# LEDArray.net
KiCad netlist of a schematic drawn in Altium Designer
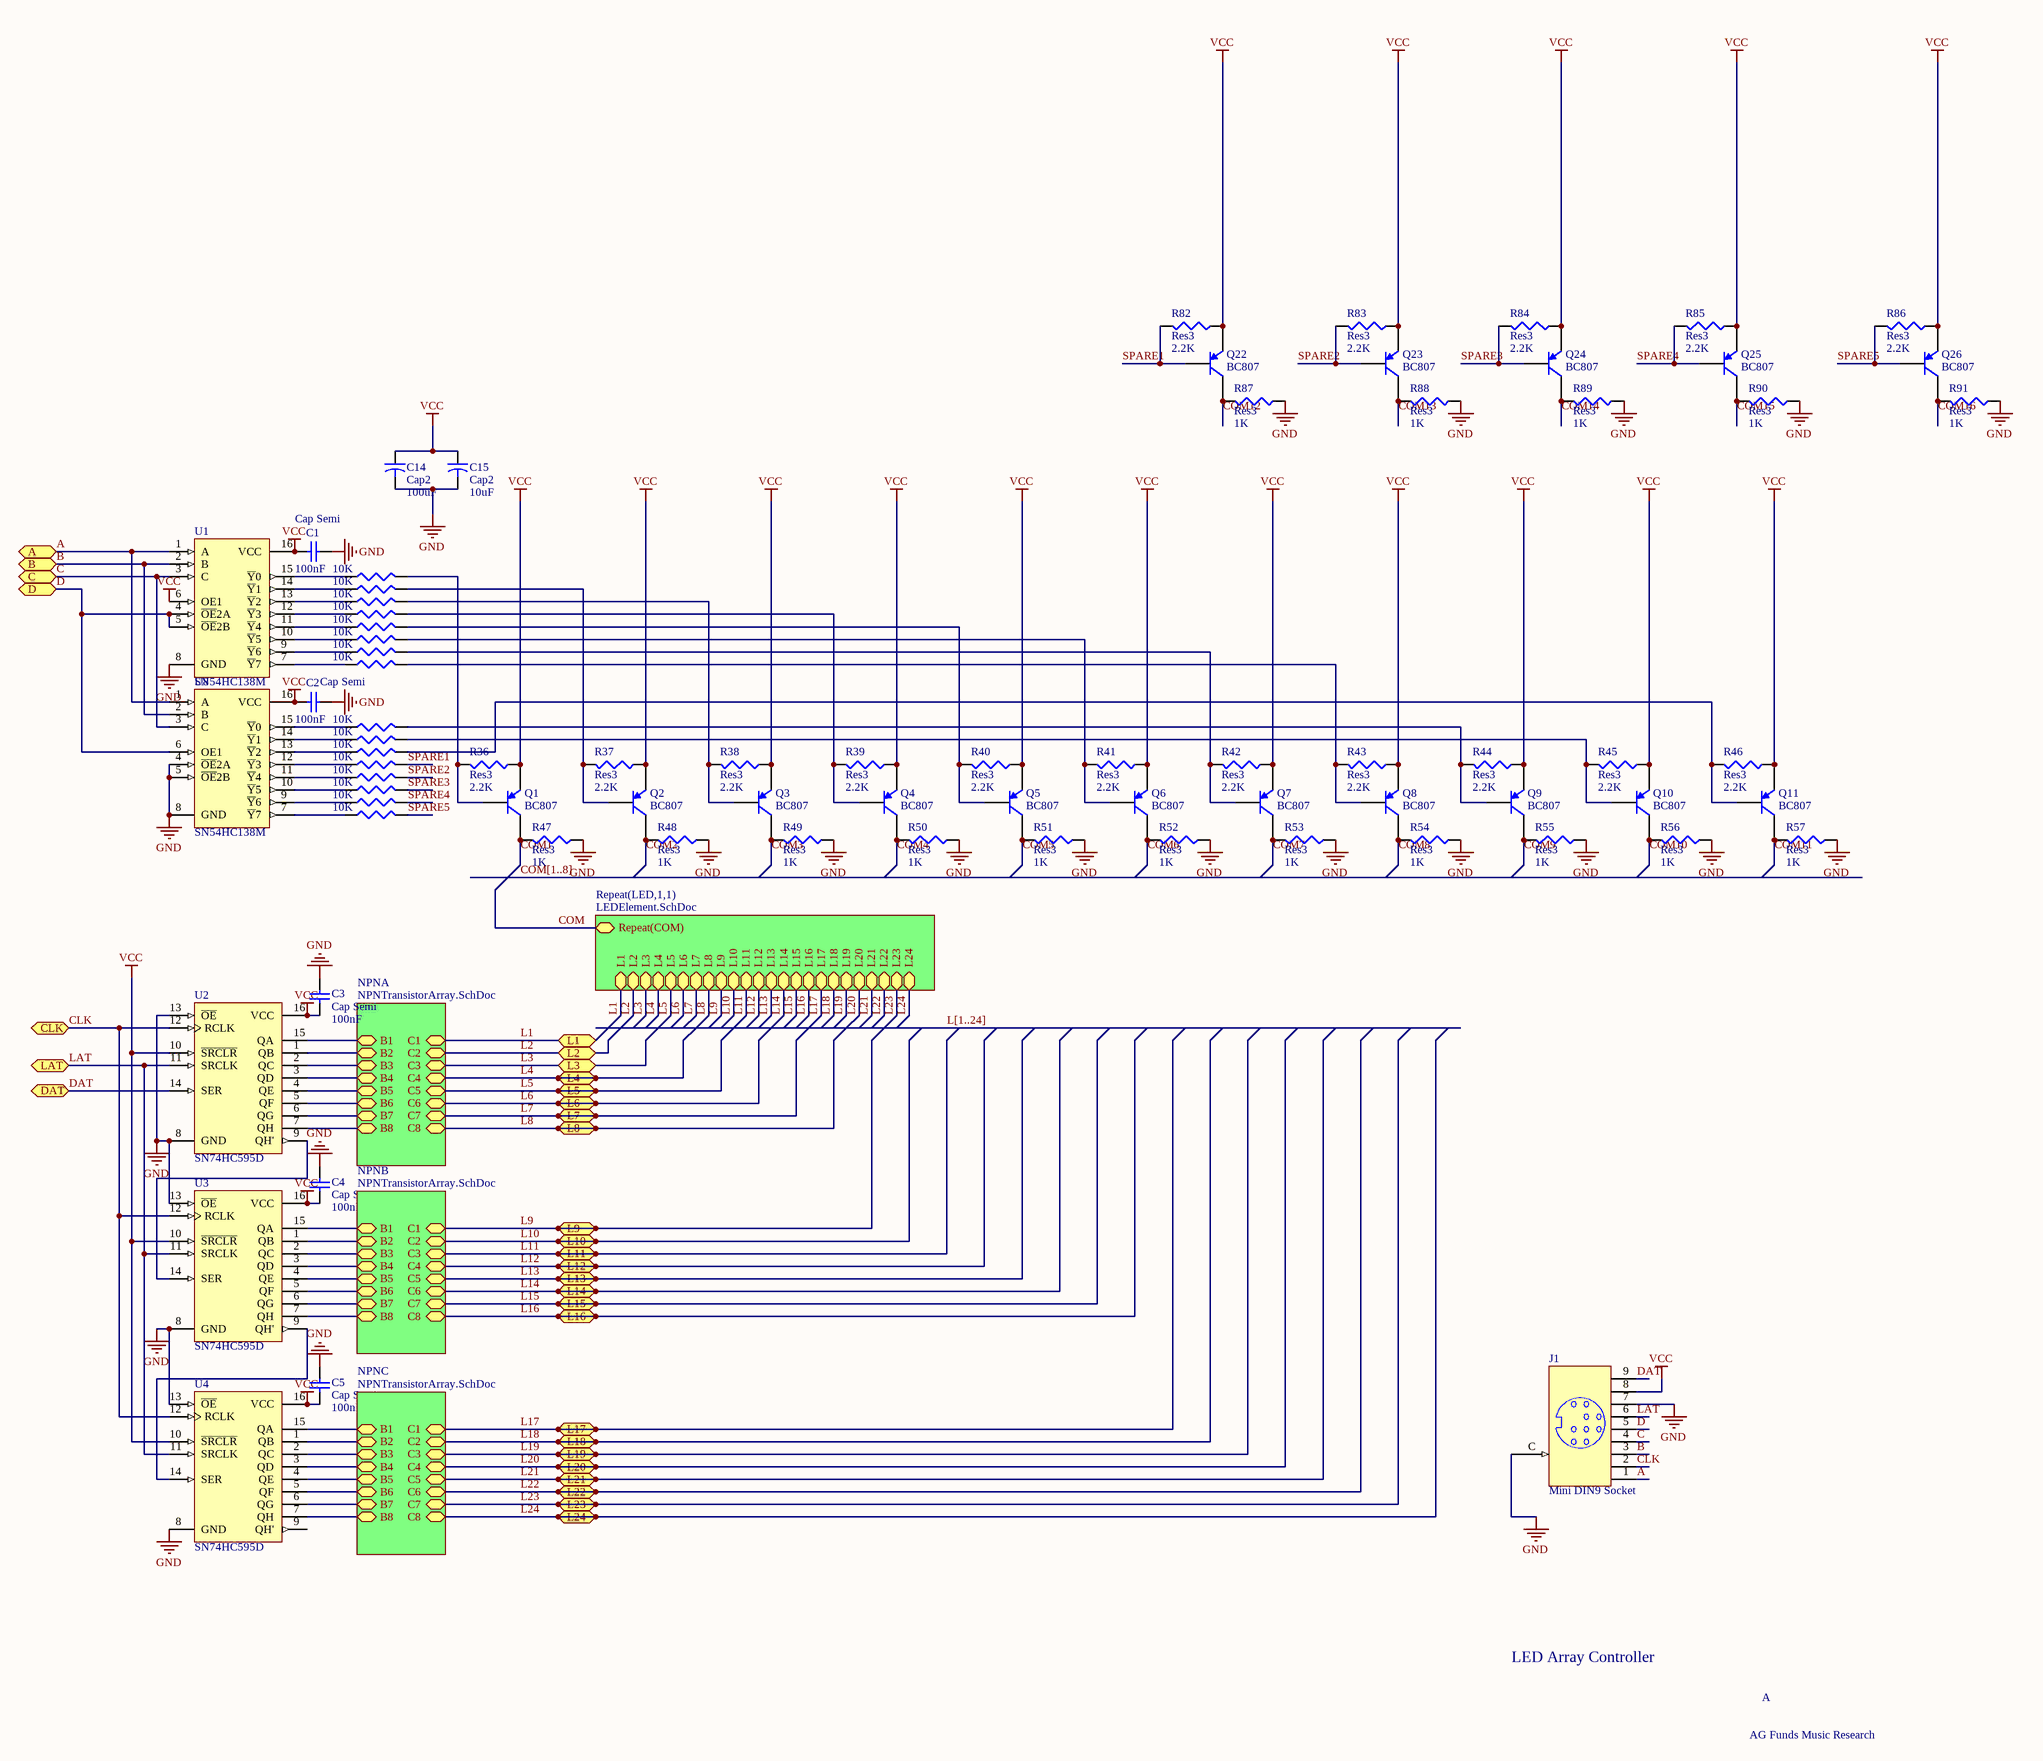
[diagram p0: LEDArray.SchDoc]

(export (version "E")
  (design (tool "Eeschema 10.0.6"))
  (components
    (comp (ref "C1")
      (value "Cap Semi")
      (footprint "1608[0603]")
      (description "Capacitor (Semiconductor SIM Model)")
      (fields (field (name "ALTIUM_VALUE") "100nF") (field (name "PUBLISHER") "Altium Limited"))
      (libsource (lib "Miscellaneous Devices") (part "Cap Semi"))
    )
    (comp (ref "C2")
      (value "Cap Semi")
      (footprint "1608[0603]")
      (description "Capacitor (Semiconductor SIM Model)")
      (fields (field (name "ALTIUM_VALUE") "100nF") (field (name "PUBLISHER") "Altium Limited"))
      (libsource (lib "Miscellaneous Devices") (part "Cap Semi"))
    )
    (comp (ref "C3")
      (value "Cap Semi")
      (footprint "1608[0603]")
      (description "Capacitor (Semiconductor SIM Model)")
      (fields (field (name "ALTIUM_VALUE") "100nF") (field (name "PUBLISHER") "Altium Limited"))
      (libsource (lib "Miscellaneous Devices") (part "Cap Semi"))
    )
    (comp (ref "C4")
      (value "Cap Semi")
      (footprint "1608[0603]")
      (description "Capacitor (Semiconductor SIM Model)")
      (fields (field (name "ALTIUM_VALUE") "100nF") (field (name "PUBLISHER") "Altium Limited"))
      (libsource (lib "Miscellaneous Devices") (part "Cap Semi"))
    )
    (comp (ref "C5")
      (value "Cap Semi")
      (footprint "1608[0603]")
      (description "Capacitor (Semiconductor SIM Model)")
      (fields (field (name "ALTIUM_VALUE") "100nF") (field (name "PUBLISHER") "Altium Limited"))
      (libsource (lib "Miscellaneous Devices") (part "Cap Semi"))
    )
    (comp (ref "C14")
      (value "Cap2")
      (footprint "CAPR5-4X5")
      (description "Capacitor")
      (fields (field (name "ALTIUM_VALUE") "100uF") (field (name "PUBLISHER") "Altium Limited"))
      (libsource (lib "Miscellaneous Devices") (part "Cap2"))
    )
    (comp (ref "C15")
      (value "Cap2")
      (footprint "CAPR5-4X5")
      (description "Capacitor")
      (fields (field (name "ALTIUM_VALUE") "10uF") (field (name "PUBLISHER") "Altium Limited"))
      (libsource (lib "Miscellaneous Devices") (part "Cap2"))
    )
    (comp (ref "J1")
      (value "Mini DIN9 Socket")
      (footprint "RGBLED:9miniDIN")
      (description "CUI Inc. MD-90S MINIDIN9 PCB Mount Socket")
      (fields (field (name "PUBLISHER") "Altium Limited"))
      (libsource (lib "MIDIPiano_7") (part "mDIN9"))
    )
    (comp (ref "Q1")
      (value "BC807")
      (footprint "SOT23-3M")
      (description "BC807 PNP General Purpose Amplifier")
      (libsource (lib "MIDIPiano_7") (part "BC807"))
    )
    (comp (ref "Q2")
      (value "BC807")
      (footprint "SOT23-3M")
      (description "BC807 PNP General Purpose Amplifier")
      (libsource (lib "MIDIPiano_7") (part "BC807"))
    )
    (comp (ref "Q3")
      (value "BC807")
      (footprint "SOT23-3M")
      (description "BC807 PNP General Purpose Amplifier")
      (libsource (lib "MIDIPiano_7") (part "BC807"))
    )
    (comp (ref "Q4")
      (value "BC807")
      (footprint "SOT23-3M")
      (description "BC807 PNP General Purpose Amplifier")
      (libsource (lib "MIDIPiano_7") (part "BC807"))
    )
    (comp (ref "Q5")
      (value "BC807")
      (footprint "SOT23-3M")
      (description "BC807 PNP General Purpose Amplifier")
      (libsource (lib "MIDIPiano_7") (part "BC807"))
    )
    (comp (ref "Q6")
      (value "BC807")
      (footprint "SOT23-3M")
      (description "BC807 PNP General Purpose Amplifier")
      (libsource (lib "MIDIPiano_7") (part "BC807"))
    )
    (comp (ref "Q7")
      (value "BC807")
      (footprint "SOT23-3M")
      (description "BC807 PNP General Purpose Amplifier")
      (libsource (lib "MIDIPiano_7") (part "BC807"))
    )
    (comp (ref "Q8")
      (value "BC807")
      (footprint "SOT23-3M")
      (description "BC807 PNP General Purpose Amplifier")
      (libsource (lib "MIDIPiano_7") (part "BC807"))
    )
    (comp (ref "Q9")
      (value "BC807")
      (footprint "SOT23-3M")
      (description "BC807 PNP General Purpose Amplifier")
      (libsource (lib "MIDIPiano_7") (part "BC807"))
    )
    (comp (ref "Q10")
      (value "BC807")
      (footprint "SOT23-3M")
      (description "BC807 PNP General Purpose Amplifier")
      (libsource (lib "MIDIPiano_7") (part "BC807"))
    )
    (comp (ref "Q11")
      (value "BC807")
      (footprint "SOT23-3M")
      (description "BC807 PNP General Purpose Amplifier")
      (libsource (lib "MIDIPiano_7") (part "BC807"))
    )
    (comp (ref "Q22")
      (value "BC807")
      (footprint "SOT23-3M")
      (description "BC807 PNP General Purpose Amplifier")
      (libsource (lib "MIDIPiano_7") (part "BC807"))
    )
    (comp (ref "Q23")
      (value "BC807")
      (footprint "SOT23-3M")
      (description "BC807 PNP General Purpose Amplifier")
      (libsource (lib "MIDIPiano_7") (part "BC807"))
    )
    (comp (ref "Q24")
      (value "BC807")
      (footprint "SOT23-3M")
      (description "BC807 PNP General Purpose Amplifier")
      (libsource (lib "MIDIPiano_7") (part "BC807"))
    )
    (comp (ref "Q25")
      (value "BC807")
      (footprint "SOT23-3M")
      (description "BC807 PNP General Purpose Amplifier")
      (libsource (lib "MIDIPiano_7") (part "BC807"))
    )
    (comp (ref "Q26")
      (value "BC807")
      (footprint "SOT23-3M")
      (description "BC807 PNP General Purpose Amplifier")
      (libsource (lib "MIDIPiano_7") (part "BC807"))
    )
    (comp (ref "R25")
      (value "10K")
      (footprint "J1-0603")
      (description "Resistor")
      (fields (field (name "Comment") "Res3") (field (name "PUBLISHER") "Altium Limited"))
      (libsource (lib "Miscellaneous Devices") (part "Res3"))
    )
    (comp (ref "R26")
      (value "10K")
      (footprint "J1-0603")
      (description "Resistor")
      (fields (field (name "Comment") "Res3") (field (name "PUBLISHER") "Altium Limited"))
      (libsource (lib "Miscellaneous Devices") (part "Res3"))
    )
    (comp (ref "R27")
      (value "10K")
      (footprint "J1-0603")
      (description "Resistor")
      (fields (field (name "Comment") "Res3") (field (name "PUBLISHER") "Altium Limited"))
      (libsource (lib "Miscellaneous Devices") (part "Res3"))
    )
    (comp (ref "R28")
      (value "10K")
      (footprint "J1-0603")
      (description "Resistor")
      (fields (field (name "Comment") "Res3") (field (name "PUBLISHER") "Altium Limited"))
      (libsource (lib "Miscellaneous Devices") (part "Res3"))
    )
    (comp (ref "R29")
      (value "10K")
      (footprint "J1-0603")
      (description "Resistor")
      (fields (field (name "Comment") "Res3") (field (name "PUBLISHER") "Altium Limited"))
      (libsource (lib "Miscellaneous Devices") (part "Res3"))
    )
    (comp (ref "R30")
      (value "10K")
      (footprint "J1-0603")
      (description "Resistor")
      (fields (field (name "Comment") "Res3") (field (name "PUBLISHER") "Altium Limited"))
      (libsource (lib "Miscellaneous Devices") (part "Res3"))
    )
    (comp (ref "R31")
      (value "10K")
      (footprint "J1-0603")
      (description "Resistor")
      (fields (field (name "Comment") "Res3") (field (name "PUBLISHER") "Altium Limited"))
      (libsource (lib "Miscellaneous Devices") (part "Res3"))
    )
    (comp (ref "R32")
      (value "10K")
      (footprint "J1-0603")
      (description "Resistor")
      (fields (field (name "Comment") "Res3") (field (name "PUBLISHER") "Altium Limited"))
      (libsource (lib "Miscellaneous Devices") (part "Res3"))
    )
    (comp (ref "R33")
      (value "10K")
      (footprint "J1-0603")
      (description "Resistor")
      (fields (field (name "Comment") "Res3") (field (name "PUBLISHER") "Altium Limited"))
      (libsource (lib "Miscellaneous Devices") (part "Res3"))
    )
    (comp (ref "R34")
      (value "10K")
      (footprint "J1-0603")
      (description "Resistor")
      (fields (field (name "Comment") "Res3") (field (name "PUBLISHER") "Altium Limited"))
      (libsource (lib "Miscellaneous Devices") (part "Res3"))
    )
    (comp (ref "R35")
      (value "10K")
      (footprint "J1-0603")
      (description "Resistor")
      (fields (field (name "Comment") "Res3") (field (name "PUBLISHER") "Altium Limited"))
      (libsource (lib "Miscellaneous Devices") (part "Res3"))
    )
    (comp (ref "R36")
      (value "Res3")
      (footprint "J1-0603")
      (description "Resistor")
      (fields (field (name "ALTIUM_VALUE") "2.2K") (field (name "PUBLISHER") "Altium Limited"))
      (libsource (lib "Miscellaneous Devices") (part "Res3"))
    )
    (comp (ref "R37")
      (value "Res3")
      (footprint "J1-0603")
      (description "Resistor")
      (fields (field (name "ALTIUM_VALUE") "2.2K") (field (name "PUBLISHER") "Altium Limited"))
      (libsource (lib "Miscellaneous Devices") (part "Res3"))
    )
    (comp (ref "R38")
      (value "Res3")
      (footprint "J1-0603")
      (description "Resistor")
      (fields (field (name "ALTIUM_VALUE") "2.2K") (field (name "PUBLISHER") "Altium Limited"))
      (libsource (lib "Miscellaneous Devices") (part "Res3"))
    )
    (comp (ref "R39")
      (value "Res3")
      (footprint "J1-0603")
      (description "Resistor")
      (fields (field (name "ALTIUM_VALUE") "2.2K") (field (name "PUBLISHER") "Altium Limited"))
      (libsource (lib "Miscellaneous Devices") (part "Res3"))
    )
    (comp (ref "R40")
      (value "Res3")
      (footprint "J1-0603")
      (description "Resistor")
      (fields (field (name "ALTIUM_VALUE") "2.2K") (field (name "PUBLISHER") "Altium Limited"))
      (libsource (lib "Miscellaneous Devices") (part "Res3"))
    )
    (comp (ref "R41")
      (value "Res3")
      (footprint "J1-0603")
      (description "Resistor")
      (fields (field (name "ALTIUM_VALUE") "2.2K") (field (name "PUBLISHER") "Altium Limited"))
      (libsource (lib "Miscellaneous Devices") (part "Res3"))
    )
    (comp (ref "R42")
      (value "Res3")
      (footprint "J1-0603")
      (description "Resistor")
      (fields (field (name "ALTIUM_VALUE") "2.2K") (field (name "PUBLISHER") "Altium Limited"))
      (libsource (lib "Miscellaneous Devices") (part "Res3"))
    )
    (comp (ref "R43")
      (value "Res3")
      (footprint "J1-0603")
      (description "Resistor")
      (fields (field (name "ALTIUM_VALUE") "2.2K") (field (name "PUBLISHER") "Altium Limited"))
      (libsource (lib "Miscellaneous Devices") (part "Res3"))
    )
    (comp (ref "R44")
      (value "Res3")
      (footprint "J1-0603")
      (description "Resistor")
      (fields (field (name "ALTIUM_VALUE") "2.2K") (field (name "PUBLISHER") "Altium Limited"))
      (libsource (lib "Miscellaneous Devices") (part "Res3"))
    )
    (comp (ref "R45")
      (value "Res3")
      (footprint "J1-0603")
      (description "Resistor")
      (fields (field (name "ALTIUM_VALUE") "2.2K") (field (name "PUBLISHER") "Altium Limited"))
      (libsource (lib "Miscellaneous Devices") (part "Res3"))
    )
    (comp (ref "R46")
      (value "Res3")
      (footprint "J1-0603")
      (description "Resistor")
      (fields (field (name "ALTIUM_VALUE") "2.2K") (field (name "PUBLISHER") "Altium Limited"))
      (libsource (lib "Miscellaneous Devices") (part "Res3"))
    )
    (comp (ref "R47")
      (value "Res3")
      (footprint "J1-0603")
      (description "Resistor")
      (fields (field (name "ALTIUM_VALUE") "1K") (field (name "PUBLISHER") "Altium Limited"))
      (libsource (lib "Miscellaneous Devices") (part "Res3"))
    )
    (comp (ref "R48")
      (value "Res3")
      (footprint "J1-0603")
      (description "Resistor")
      (fields (field (name "ALTIUM_VALUE") "1K") (field (name "PUBLISHER") "Altium Limited"))
      (libsource (lib "Miscellaneous Devices") (part "Res3"))
    )
    (comp (ref "R49")
      (value "Res3")
      (footprint "J1-0603")
      (description "Resistor")
      (fields (field (name "ALTIUM_VALUE") "1K") (field (name "PUBLISHER") "Altium Limited"))
      (libsource (lib "Miscellaneous Devices") (part "Res3"))
    )
    (comp (ref "R50")
      (value "Res3")
      (footprint "J1-0603")
      (description "Resistor")
      (fields (field (name "ALTIUM_VALUE") "1K") (field (name "PUBLISHER") "Altium Limited"))
      (libsource (lib "Miscellaneous Devices") (part "Res3"))
    )
    (comp (ref "R51")
      (value "Res3")
      (footprint "J1-0603")
      (description "Resistor")
      (fields (field (name "ALTIUM_VALUE") "1K") (field (name "PUBLISHER") "Altium Limited"))
      (libsource (lib "Miscellaneous Devices") (part "Res3"))
    )
    (comp (ref "R52")
      (value "Res3")
      (footprint "J1-0603")
      (description "Resistor")
      (fields (field (name "ALTIUM_VALUE") "1K") (field (name "PUBLISHER") "Altium Limited"))
      (libsource (lib "Miscellaneous Devices") (part "Res3"))
    )
    (comp (ref "R53")
      (value "Res3")
      (footprint "J1-0603")
      (description "Resistor")
      (fields (field (name "ALTIUM_VALUE") "1K") (field (name "PUBLISHER") "Altium Limited"))
      (libsource (lib "Miscellaneous Devices") (part "Res3"))
    )
    (comp (ref "R54")
      (value "Res3")
      (footprint "J1-0603")
      (description "Resistor")
      (fields (field (name "ALTIUM_VALUE") "1K") (field (name "PUBLISHER") "Altium Limited"))
      (libsource (lib "Miscellaneous Devices") (part "Res3"))
    )
    (comp (ref "R55")
      (value "Res3")
      (footprint "J1-0603")
      (description "Resistor")
      (fields (field (name "ALTIUM_VALUE") "1K") (field (name "PUBLISHER") "Altium Limited"))
      (libsource (lib "Miscellaneous Devices") (part "Res3"))
    )
    (comp (ref "R56")
      (value "Res3")
      (footprint "J1-0603")
      (description "Resistor")
      (fields (field (name "ALTIUM_VALUE") "1K") (field (name "PUBLISHER") "Altium Limited"))
      (libsource (lib "Miscellaneous Devices") (part "Res3"))
    )
    (comp (ref "R57")
      (value "Res3")
      (footprint "J1-0603")
      (description "Resistor")
      (fields (field (name "ALTIUM_VALUE") "1K") (field (name "PUBLISHER") "Altium Limited"))
      (libsource (lib "Miscellaneous Devices") (part "Res3"))
    )
    (comp (ref "R82")
      (value "Res3")
      (footprint "J1-0603")
      (description "Resistor")
      (fields (field (name "ALTIUM_VALUE") "2.2K") (field (name "PUBLISHER") "Altium Limited"))
      (libsource (lib "Miscellaneous Devices") (part "Res3"))
    )
    (comp (ref "R83")
      (value "Res3")
      (footprint "J1-0603")
      (description "Resistor")
      (fields (field (name "ALTIUM_VALUE") "2.2K") (field (name "PUBLISHER") "Altium Limited"))
      (libsource (lib "Miscellaneous Devices") (part "Res3"))
    )
    (comp (ref "R84")
      (value "Res3")
      (footprint "J1-0603")
      (description "Resistor")
      (fields (field (name "ALTIUM_VALUE") "2.2K") (field (name "PUBLISHER") "Altium Limited"))
      (libsource (lib "Miscellaneous Devices") (part "Res3"))
    )
    (comp (ref "R85")
      (value "Res3")
      (footprint "J1-0603")
      (description "Resistor")
      (fields (field (name "ALTIUM_VALUE") "2.2K") (field (name "PUBLISHER") "Altium Limited"))
      (libsource (lib "Miscellaneous Devices") (part "Res3"))
    )
    (comp (ref "R86")
      (value "Res3")
      (footprint "J1-0603")
      (description "Resistor")
      (fields (field (name "ALTIUM_VALUE") "2.2K") (field (name "PUBLISHER") "Altium Limited"))
      (libsource (lib "Miscellaneous Devices") (part "Res3"))
    )
    (comp (ref "R87")
      (value "Res3")
      (footprint "J1-0603")
      (description "Resistor")
      (fields (field (name "ALTIUM_VALUE") "1K") (field (name "PUBLISHER") "Altium Limited"))
      (libsource (lib "Miscellaneous Devices") (part "Res3"))
    )
    (comp (ref "R88")
      (value "Res3")
      (footprint "J1-0603")
      (description "Resistor")
      (fields (field (name "ALTIUM_VALUE") "1K") (field (name "PUBLISHER") "Altium Limited"))
      (libsource (lib "Miscellaneous Devices") (part "Res3"))
    )
    (comp (ref "R89")
      (value "Res3")
      (footprint "J1-0603")
      (description "Resistor")
      (fields (field (name "ALTIUM_VALUE") "1K") (field (name "PUBLISHER") "Altium Limited"))
      (libsource (lib "Miscellaneous Devices") (part "Res3"))
    )
    (comp (ref "R90")
      (value "Res3")
      (footprint "J1-0603")
      (description "Resistor")
      (fields (field (name "ALTIUM_VALUE") "1K") (field (name "PUBLISHER") "Altium Limited"))
      (libsource (lib "Miscellaneous Devices") (part "Res3"))
    )
    (comp (ref "R91")
      (value "Res3")
      (footprint "J1-0603")
      (description "Resistor")
      (fields (field (name "ALTIUM_VALUE") "1K") (field (name "PUBLISHER") "Altium Limited"))
      (libsource (lib "Miscellaneous Devices") (part "Res3"))
    )
    (comp (ref "R92")
      (value "10K")
      (footprint "J1-0603")
      (description "Resistor")
      (fields (field (name "Comment") "Res3") (field (name "PUBLISHER") "Altium Limited"))
      (libsource (lib "Miscellaneous Devices") (part "Res3"))
    )
    (comp (ref "R93")
      (value "10K")
      (footprint "J1-0603")
      (description "Resistor")
      (fields (field (name "Comment") "Res3") (field (name "PUBLISHER") "Altium Limited"))
      (libsource (lib "Miscellaneous Devices") (part "Res3"))
    )
    (comp (ref "R94")
      (value "10K")
      (footprint "J1-0603")
      (description "Resistor")
      (fields (field (name "Comment") "Res3") (field (name "PUBLISHER") "Altium Limited"))
      (libsource (lib "Miscellaneous Devices") (part "Res3"))
    )
    (comp (ref "R95")
      (value "10K")
      (footprint "J1-0603")
      (description "Resistor")
      (fields (field (name "Comment") "Res3") (field (name "PUBLISHER") "Altium Limited"))
      (libsource (lib "Miscellaneous Devices") (part "Res3"))
    )
    (comp (ref "R96")
      (value "10K")
      (footprint "J1-0603")
      (description "Resistor")
      (fields (field (name "Comment") "Res3") (field (name "PUBLISHER") "Altium Limited"))
      (libsource (lib "Miscellaneous Devices") (part "Res3"))
    )
    (comp (ref "U1")
      (value "SN54HC138M")
      (footprint "SOIC127P602-16BM")
      (description "3-Line to 8-Line Decoder / Demultiplexer")
      (fields (field (name "PUBLISHER") "Altium Limited"))
      (libsource (lib "MIDIPiano_1") (part "SN54HC138J"))
    )
    (comp (ref "U2")
      (value "SN74HC595D")
      (footprint "D016_N")
      (description "8-Bit Shift Register with 3-State Output Registers")
      (fields (field (name "PUBLISHER") "Altium Limited"))
      (libsource (lib "MIDIPiano_7") (part "SN74HC595D"))
    )
    (comp (ref "U3")
      (value "SN74HC595D")
      (footprint "D016_N")
      (description "8-Bit Shift Register with 3-State Output Registers")
      (fields (field (name "PUBLISHER") "Altium Limited"))
      (libsource (lib "MIDIPiano_7") (part "SN74HC595D"))
    )
    (comp (ref "U4")
      (value "SN74HC595D")
      (footprint "D016_N")
      (description "8-Bit Shift Register with 3-State Output Registers")
      (fields (field (name "PUBLISHER") "Altium Limited"))
      (libsource (lib "MIDIPiano_7") (part "SN74HC595D"))
    )
    (comp (ref "U8")
      (value "SN54HC138M")
      (footprint "SOIC127P602-16BM")
      (description "3-Line to 8-Line Decoder / Demultiplexer")
      (fields (field (name "PUBLISHER") "Altium Limited"))
      (libsource (lib "MIDIPiano_1") (part "SN54HC138J"))
    )
  )
  (nets
    (net (code "1") (name "/A") (class "Default")
      (node (ref "J1") (pin "1") (pinfunction "1_1") (pintype "passive"))
      (node (ref "U1") (pin "1") (pinfunction "A_1") (pintype "input"))
      (node (ref "U8") (pin "1") (pinfunction "A_1") (pintype "input"))
    )
    (net (code "2") (name "/B") (class "Default")
      (node (ref "J1") (pin "3") (pinfunction "3_3") (pintype "passive"))
      (node (ref "U1") (pin "2") (pinfunction "B_2") (pintype "input"))
      (node (ref "U8") (pin "2") (pinfunction "B_2") (pintype "input"))
    )
    (net (code "3") (name "/B1") (class "Default")
      (node (ref "U4") (pin "15") (pinfunction "QA_15") (pintype "tri_state"))
    )
    (net (code "4") (name "/B1_1") (class "Default")
      (node (ref "U2") (pin "15") (pinfunction "QA_15") (pintype "tri_state"))
    )
    (net (code "5") (name "/B1_2") (class "Default")
      (node (ref "U3") (pin "15") (pinfunction "QA_15") (pintype "tri_state"))
    )
    (net (code "6") (name "/B2") (class "Default")
      (node (ref "U4") (pin "1") (pinfunction "QB_1") (pintype "tri_state"))
    )
    (net (code "7") (name "/B2_1") (class "Default")
      (node (ref "U2") (pin "1") (pinfunction "QB_1") (pintype "tri_state"))
    )
    (net (code "8") (name "/B2_2") (class "Default")
      (node (ref "U3") (pin "1") (pinfunction "QB_1") (pintype "tri_state"))
    )
    (net (code "9") (name "/B3") (class "Default")
      (node (ref "U4") (pin "2") (pinfunction "QC_2") (pintype "tri_state"))
    )
    (net (code "10") (name "/B3_1") (class "Default")
      (node (ref "U2") (pin "2") (pinfunction "QC_2") (pintype "tri_state"))
    )
    (net (code "11") (name "/B3_2") (class "Default")
      (node (ref "U3") (pin "2") (pinfunction "QC_2") (pintype "tri_state"))
    )
    (net (code "12") (name "/B4") (class "Default")
      (node (ref "U4") (pin "3") (pinfunction "QD_3") (pintype "tri_state"))
    )
    (net (code "13") (name "/B4_1") (class "Default")
      (node (ref "U2") (pin "3") (pinfunction "QD_3") (pintype "tri_state"))
    )
    (net (code "14") (name "/B4_2") (class "Default")
      (node (ref "U3") (pin "3") (pinfunction "QD_3") (pintype "tri_state"))
    )
    (net (code "15") (name "/B5") (class "Default")
      (node (ref "U4") (pin "4") (pinfunction "QE_4") (pintype "tri_state"))
    )
    (net (code "16") (name "/B5_1") (class "Default")
      (node (ref "U2") (pin "4") (pinfunction "QE_4") (pintype "tri_state"))
    )
    (net (code "17") (name "/B5_2") (class "Default")
      (node (ref "U3") (pin "4") (pinfunction "QE_4") (pintype "tri_state"))
    )
    (net (code "18") (name "/B6") (class "Default")
      (node (ref "U4") (pin "5") (pinfunction "QF_5") (pintype "tri_state"))
    )
    (net (code "19") (name "/B6_1") (class "Default")
      (node (ref "U2") (pin "5") (pinfunction "QF_5") (pintype "tri_state"))
    )
    (net (code "20") (name "/B6_2") (class "Default")
      (node (ref "U3") (pin "5") (pinfunction "QF_5") (pintype "tri_state"))
    )
    (net (code "21") (name "/B7") (class "Default")
      (node (ref "U4") (pin "6") (pinfunction "QG_6") (pintype "tri_state"))
    )
    (net (code "22") (name "/B7_1") (class "Default")
      (node (ref "U2") (pin "6") (pinfunction "QG_6") (pintype "tri_state"))
    )
    (net (code "23") (name "/B7_2") (class "Default")
      (node (ref "U3") (pin "6") (pinfunction "QG_6") (pintype "tri_state"))
    )
    (net (code "24") (name "/B8") (class "Default")
      (node (ref "U4") (pin "7") (pinfunction "QH_7") (pintype "tri_state"))
    )
    (net (code "25") (name "/B8_1") (class "Default")
      (node (ref "U2") (pin "7") (pinfunction "QH_7") (pintype "tri_state"))
    )
    (net (code "26") (name "/B8_2") (class "Default")
      (node (ref "U3") (pin "7") (pinfunction "QH_7") (pintype "tri_state"))
    )
    (net (code "27") (name "/C") (class "Default")
      (node (ref "J1") (pin "4") (pinfunction "4_4") (pintype "passive"))
      (node (ref "U1") (pin "3") (pinfunction "C_3") (pintype "input"))
      (node (ref "U8") (pin "3") (pinfunction "C_3") (pintype "input"))
    )
    (net (code "28") (name "/CLK") (class "Default")
      (node (ref "J1") (pin "2") (pinfunction "2_2") (pintype "passive"))
      (node (ref "U2") (pin "12") (pinfunction "RCLK_12") (pintype "input"))
      (node (ref "U3") (pin "12") (pinfunction "RCLK_12") (pintype "input"))
      (node (ref "U4") (pin "12") (pinfunction "RCLK_12") (pintype "input"))
    )
    (net (code "30") (name "/COM1") (class "Default")
      (node (ref "Q1") (pin "3") (pinfunction "C_3") (pintype "passive"))
      (node (ref "R47") (pin "2") (pinfunction "2_2") (pintype "passive"))
    )
    (net (code "31") (name "/COM2") (class "Default")
      (node (ref "Q2") (pin "3") (pinfunction "C_3") (pintype "passive"))
      (node (ref "R48") (pin "2") (pinfunction "2_2") (pintype "passive"))
    )
    (net (code "32") (name "/COM3") (class "Default")
      (node (ref "Q3") (pin "3") (pinfunction "C_3") (pintype "passive"))
      (node (ref "R49") (pin "2") (pinfunction "2_2") (pintype "passive"))
    )
    (net (code "33") (name "/COM4") (class "Default")
      (node (ref "Q4") (pin "3") (pinfunction "C_3") (pintype "passive"))
      (node (ref "R50") (pin "2") (pinfunction "2_2") (pintype "passive"))
    )
    (net (code "34") (name "/COM5") (class "Default")
      (node (ref "Q5") (pin "3") (pinfunction "C_3") (pintype "passive"))
      (node (ref "R51") (pin "2") (pinfunction "2_2") (pintype "passive"))
    )
    (net (code "35") (name "/COM6") (class "Default")
      (node (ref "Q6") (pin "3") (pinfunction "C_3") (pintype "passive"))
      (node (ref "R52") (pin "2") (pinfunction "2_2") (pintype "passive"))
    )
    (net (code "36") (name "/COM7") (class "Default")
      (node (ref "Q7") (pin "3") (pinfunction "C_3") (pintype "passive"))
      (node (ref "R53") (pin "2") (pinfunction "2_2") (pintype "passive"))
    )
    (net (code "37") (name "/COM8") (class "Default")
      (node (ref "Q8") (pin "3") (pinfunction "C_3") (pintype "passive"))
      (node (ref "R54") (pin "2") (pinfunction "2_2") (pintype "passive"))
    )
    (net (code "38") (name "/COM9") (class "Default")
      (node (ref "Q9") (pin "3") (pinfunction "C_3") (pintype "passive"))
      (node (ref "R55") (pin "2") (pinfunction "2_2") (pintype "passive"))
    )
    (net (code "39") (name "/COM10") (class "Default")
      (node (ref "Q10") (pin "3") (pinfunction "C_3") (pintype "passive"))
      (node (ref "R56") (pin "2") (pinfunction "2_2") (pintype "passive"))
    )
    (net (code "40") (name "/COM11") (class "Default")
      (node (ref "Q11") (pin "3") (pinfunction "C_3") (pintype "passive"))
      (node (ref "R57") (pin "2") (pinfunction "2_2") (pintype "passive"))
    )
    (net (code "41") (name "/COM12") (class "Default")
      (node (ref "Q22") (pin "3") (pinfunction "C_3") (pintype "passive"))
      (node (ref "R87") (pin "2") (pinfunction "2_2") (pintype "passive"))
    )
    (net (code "42") (name "/COM13") (class "Default")
      (node (ref "Q23") (pin "3") (pinfunction "C_3") (pintype "passive"))
      (node (ref "R88") (pin "2") (pinfunction "2_2") (pintype "passive"))
    )
    (net (code "43") (name "/COM14") (class "Default")
      (node (ref "Q24") (pin "3") (pinfunction "C_3") (pintype "passive"))
      (node (ref "R89") (pin "2") (pinfunction "2_2") (pintype "passive"))
    )
    (net (code "44") (name "/COM15") (class "Default")
      (node (ref "Q25") (pin "3") (pinfunction "C_3") (pintype "passive"))
      (node (ref "R90") (pin "2") (pinfunction "2_2") (pintype "passive"))
    )
    (net (code "45") (name "/COM16") (class "Default")
      (node (ref "Q26") (pin "3") (pinfunction "C_3") (pintype "passive"))
      (node (ref "R91") (pin "2") (pinfunction "2_2") (pintype "passive"))
    )
    (net (code "47") (name "/D") (class "Default")
      (node (ref "J1") (pin "5") (pinfunction "5_5") (pintype "passive"))
      (node (ref "U1") (pin "4") (pinfunction "~{OE}2A_4") (pintype "input"))
      (node (ref "U1") (pin "5") (pinfunction "~{OE}2B_5") (pintype "input"))
      (node (ref "U8") (pin "6") (pinfunction "OE1_6") (pintype "input"))
    )
    (net (code "48") (name "/DAT") (class "Default")
      (node (ref "J1") (pin "9") (pinfunction "9_9") (pintype "passive"))
      (node (ref "U2") (pin "14") (pinfunction "SER_14") (pintype "input"))
    )
    (net (code "73") (name "/LAT") (class "Default")
      (node (ref "J1") (pin "6") (pinfunction "6_6") (pintype "passive"))
      (node (ref "U2") (pin "11") (pinfunction "SRCLK_11") (pintype "input"))
      (node (ref "U3") (pin "11") (pinfunction "SRCLK_11") (pintype "input"))
      (node (ref "U4") (pin "11") (pinfunction "SRCLK_11") (pintype "input"))
    )
    (net (code "75") (name "/SPARE1") (class "Default")
      (node (ref "Q22") (pin "1") (pinfunction "B_1") (pintype "passive"))
      (node (ref "R82") (pin "2") (pinfunction "2_2") (pintype "passive"))
      (node (ref "R92") (pin "2") (pinfunction "2_2") (pintype "passive"))
    )
    (net (code "76") (name "/SPARE2") (class "Default")
      (node (ref "Q23") (pin "1") (pinfunction "B_1") (pintype "passive"))
      (node (ref "R83") (pin "2") (pinfunction "2_2") (pintype "passive"))
      (node (ref "R93") (pin "2") (pinfunction "2_2") (pintype "passive"))
    )
    (net (code "77") (name "/SPARE3") (class "Default")
      (node (ref "Q24") (pin "1") (pinfunction "B_1") (pintype "passive"))
      (node (ref "R84") (pin "2") (pinfunction "2_2") (pintype "passive"))
      (node (ref "R94") (pin "2") (pinfunction "2_2") (pintype "passive"))
    )
    (net (code "78") (name "/SPARE4") (class "Default")
      (node (ref "Q25") (pin "1") (pinfunction "B_1") (pintype "passive"))
      (node (ref "R85") (pin "2") (pinfunction "2_2") (pintype "passive"))
      (node (ref "R95") (pin "2") (pinfunction "2_2") (pintype "passive"))
    )
    (net (code "79") (name "/SPARE5") (class "Default")
      (node (ref "Q26") (pin "1") (pinfunction "B_1") (pintype "passive"))
      (node (ref "R86") (pin "2") (pinfunction "2_2") (pintype "passive"))
      (node (ref "R96") (pin "2") (pinfunction "2_2") (pintype "passive"))
    )
    (net (code "80") (name "GND") (class "Default")
      (node (ref "C1") (pin "2") (pinfunction "2_2") (pintype "passive"))
      (node (ref "C14") (pin "2") (pinfunction "2_2") (pintype "passive"))
      (node (ref "C15") (pin "2") (pinfunction "2_2") (pintype "passive"))
      (node (ref "C2") (pin "2") (pinfunction "2_2") (pintype "passive"))
      (node (ref "C3") (pin "1") (pinfunction "1_1") (pintype "passive"))
      (node (ref "C4") (pin "1") (pinfunction "1_1") (pintype "passive"))
      (node (ref "C5") (pin "1") (pinfunction "1_1") (pintype "passive"))
      (node (ref "J1") (pin "7") (pinfunction "7_7") (pintype "passive"))
      (node (ref "J1") (pin "C") (pinfunction "C_C") (pintype "input"))
      (node (ref "R47") (pin "1") (pinfunction "1_1") (pintype "passive"))
      (node (ref "R48") (pin "1") (pinfunction "1_1") (pintype "passive"))
      (node (ref "R49") (pin "1") (pinfunction "1_1") (pintype "passive"))
      (node (ref "R50") (pin "1") (pinfunction "1_1") (pintype "passive"))
      (node (ref "R51") (pin "1") (pinfunction "1_1") (pintype "passive"))
      (node (ref "R52") (pin "1") (pinfunction "1_1") (pintype "passive"))
      (node (ref "R53") (pin "1") (pinfunction "1_1") (pintype "passive"))
      (node (ref "R54") (pin "1") (pinfunction "1_1") (pintype "passive"))
      (node (ref "R55") (pin "1") (pinfunction "1_1") (pintype "passive"))
      (node (ref "R56") (pin "1") (pinfunction "1_1") (pintype "passive"))
      (node (ref "R57") (pin "1") (pinfunction "1_1") (pintype "passive"))
      (node (ref "R87") (pin "1") (pinfunction "1_1") (pintype "passive"))
      (node (ref "R88") (pin "1") (pinfunction "1_1") (pintype "passive"))
      (node (ref "R89") (pin "1") (pinfunction "1_1") (pintype "passive"))
      (node (ref "R90") (pin "1") (pinfunction "1_1") (pintype "passive"))
      (node (ref "R91") (pin "1") (pinfunction "1_1") (pintype "passive"))
      (node (ref "U1") (pin "8") (pinfunction "GND_8") (pintype "power_in"))
      (node (ref "U2") (pin "13") (pinfunction "~{OE}_13") (pintype "input"))
      (node (ref "U2") (pin "8") (pinfunction "GND_8") (pintype "power_in"))
      (node (ref "U3") (pin "13") (pinfunction "~{OE}_13") (pintype "input"))
      (node (ref "U3") (pin "8") (pinfunction "GND_8") (pintype "power_in"))
      (node (ref "U4") (pin "13") (pinfunction "~{OE}_13") (pintype "input"))
      (node (ref "U4") (pin "8") (pinfunction "GND_8") (pintype "power_in"))
      (node (ref "U8") (pin "4") (pinfunction "~{OE}2A_4") (pintype "input"))
      (node (ref "U8") (pin "5") (pinfunction "~{OE}2B_5") (pintype "input"))
      (node (ref "U8") (pin "8") (pinfunction "GND_8") (pintype "power_in"))
    )
    (net (code "81") (name "Net-(Q1-B)") (class "Default")
      (node (ref "Q1") (pin "1") (pinfunction "B_1") (pintype "passive"))
      (node (ref "R25") (pin "2") (pinfunction "2_2") (pintype "passive"))
      (node (ref "R36") (pin "2") (pinfunction "2_2") (pintype "passive"))
    )
    (net (code "82") (name "Net-(Q2-B)") (class "Default")
      (node (ref "Q2") (pin "1") (pinfunction "B_1") (pintype "passive"))
      (node (ref "R26") (pin "2") (pinfunction "2_2") (pintype "passive"))
      (node (ref "R37") (pin "2") (pinfunction "2_2") (pintype "passive"))
    )
    (net (code "83") (name "Net-(Q3-B)") (class "Default")
      (node (ref "Q3") (pin "1") (pinfunction "B_1") (pintype "passive"))
      (node (ref "R27") (pin "2") (pinfunction "2_2") (pintype "passive"))
      (node (ref "R38") (pin "2") (pinfunction "2_2") (pintype "passive"))
    )
    (net (code "84") (name "Net-(Q4-B)") (class "Default")
      (node (ref "Q4") (pin "1") (pinfunction "B_1") (pintype "passive"))
      (node (ref "R28") (pin "2") (pinfunction "2_2") (pintype "passive"))
      (node (ref "R39") (pin "2") (pinfunction "2_2") (pintype "passive"))
    )
    (net (code "85") (name "Net-(Q5-B)") (class "Default")
      (node (ref "Q5") (pin "1") (pinfunction "B_1") (pintype "passive"))
      (node (ref "R29") (pin "2") (pinfunction "2_2") (pintype "passive"))
      (node (ref "R40") (pin "2") (pinfunction "2_2") (pintype "passive"))
    )
    (net (code "86") (name "Net-(Q6-B)") (class "Default")
      (node (ref "Q6") (pin "1") (pinfunction "B_1") (pintype "passive"))
      (node (ref "R30") (pin "2") (pinfunction "2_2") (pintype "passive"))
      (node (ref "R41") (pin "2") (pinfunction "2_2") (pintype "passive"))
    )
    (net (code "87") (name "Net-(Q7-B)") (class "Default")
      (node (ref "Q7") (pin "1") (pinfunction "B_1") (pintype "passive"))
      (node (ref "R31") (pin "2") (pinfunction "2_2") (pintype "passive"))
      (node (ref "R42") (pin "2") (pinfunction "2_2") (pintype "passive"))
    )
    (net (code "88") (name "Net-(Q8-B)") (class "Default")
      (node (ref "Q8") (pin "1") (pinfunction "B_1") (pintype "passive"))
      (node (ref "R32") (pin "2") (pinfunction "2_2") (pintype "passive"))
      (node (ref "R43") (pin "2") (pinfunction "2_2") (pintype "passive"))
    )
    (net (code "89") (name "Net-(Q9-B)") (class "Default")
      (node (ref "Q9") (pin "1") (pinfunction "B_1") (pintype "passive"))
      (node (ref "R33") (pin "2") (pinfunction "2_2") (pintype "passive"))
      (node (ref "R44") (pin "2") (pinfunction "2_2") (pintype "passive"))
    )
    (net (code "90") (name "Net-(Q10-B)") (class "Default")
      (node (ref "Q10") (pin "1") (pinfunction "B_1") (pintype "passive"))
      (node (ref "R34") (pin "2") (pinfunction "2_2") (pintype "passive"))
      (node (ref "R45") (pin "2") (pinfunction "2_2") (pintype "passive"))
    )
    (net (code "91") (name "Net-(Q11-B)") (class "Default")
      (node (ref "Q11") (pin "1") (pinfunction "B_1") (pintype "passive"))
      (node (ref "R35") (pin "2") (pinfunction "2_2") (pintype "passive"))
      (node (ref "R46") (pin "2") (pinfunction "2_2") (pintype "passive"))
    )
    (net (code "92") (name "Net-(U1-~{Y}0)") (class "Default")
      (node (ref "R25") (pin "1") (pinfunction "1_1") (pintype "passive"))
      (node (ref "U1") (pin "15") (pinfunction "~{Y}0_15") (pintype "output"))
    )
    (net (code "93") (name "Net-(U1-~{Y}1)") (class "Default")
      (node (ref "R26") (pin "1") (pinfunction "1_1") (pintype "passive"))
      (node (ref "U1") (pin "14") (pinfunction "~{Y}1_14") (pintype "output"))
    )
    (net (code "94") (name "Net-(U1-~{Y}2)") (class "Default")
      (node (ref "R27") (pin "1") (pinfunction "1_1") (pintype "passive"))
      (node (ref "U1") (pin "13") (pinfunction "~{Y}2_13") (pintype "output"))
    )
    (net (code "95") (name "Net-(U1-~{Y}3)") (class "Default")
      (node (ref "R28") (pin "1") (pinfunction "1_1") (pintype "passive"))
      (node (ref "U1") (pin "12") (pinfunction "~{Y}3_12") (pintype "output"))
    )
    (net (code "96") (name "Net-(U1-~{Y}4)") (class "Default")
      (node (ref "R29") (pin "1") (pinfunction "1_1") (pintype "passive"))
      (node (ref "U1") (pin "11") (pinfunction "~{Y}4_11") (pintype "output"))
    )
    (net (code "97") (name "Net-(U1-~{Y}5)") (class "Default")
      (node (ref "R30") (pin "1") (pinfunction "1_1") (pintype "passive"))
      (node (ref "U1") (pin "10") (pinfunction "~{Y}5_10") (pintype "output"))
    )
    (net (code "98") (name "Net-(U1-~{Y}6)") (class "Default")
      (node (ref "R31") (pin "1") (pinfunction "1_1") (pintype "passive"))
      (node (ref "U1") (pin "9") (pinfunction "~{Y}6_9") (pintype "output"))
    )
    (net (code "99") (name "Net-(U1-~{Y}7)") (class "Default")
      (node (ref "R32") (pin "1") (pinfunction "1_1") (pintype "passive"))
      (node (ref "U1") (pin "7") (pinfunction "~{Y}7_7") (pintype "output"))
    )
    (net (code "100") (name "Net-(U2-QH')") (class "Default")
      (node (ref "U2") (pin "9") (pinfunction "QH'_9") (pintype "output"))
      (node (ref "U3") (pin "14") (pinfunction "SER_14") (pintype "input"))
    )
    (net (code "101") (name "Net-(U3-QH')") (class "Default")
      (node (ref "U3") (pin "9") (pinfunction "QH'_9") (pintype "output"))
      (node (ref "U4") (pin "14") (pinfunction "SER_14") (pintype "input"))
    )
    (net (code "102") (name "Net-(U8-~{Y}0)") (class "Default")
      (node (ref "R33") (pin "1") (pinfunction "1_1") (pintype "passive"))
      (node (ref "U8") (pin "15") (pinfunction "~{Y}0_15") (pintype "output"))
    )
    (net (code "103") (name "Net-(U8-~{Y}1)") (class "Default")
      (node (ref "R34") (pin "1") (pinfunction "1_1") (pintype "passive"))
      (node (ref "U8") (pin "14") (pinfunction "~{Y}1_14") (pintype "output"))
    )
    (net (code "104") (name "Net-(U8-~{Y}2)") (class "Default")
      (node (ref "R35") (pin "1") (pinfunction "1_1") (pintype "passive"))
      (node (ref "U8") (pin "13") (pinfunction "~{Y}2_13") (pintype "output"))
    )
    (net (code "105") (name "Net-(U8-~{Y}3)") (class "Default")
      (node (ref "R92") (pin "1") (pinfunction "1_1") (pintype "passive"))
      (node (ref "U8") (pin "12") (pinfunction "~{Y}3_12") (pintype "output"))
    )
    (net (code "106") (name "Net-(U8-~{Y}4)") (class "Default")
      (node (ref "R93") (pin "1") (pinfunction "1_1") (pintype "passive"))
      (node (ref "U8") (pin "11") (pinfunction "~{Y}4_11") (pintype "output"))
    )
    (net (code "107") (name "Net-(U8-~{Y}5)") (class "Default")
      (node (ref "R94") (pin "1") (pinfunction "1_1") (pintype "passive"))
      (node (ref "U8") (pin "10") (pinfunction "~{Y}5_10") (pintype "output"))
    )
    (net (code "108") (name "Net-(U8-~{Y}6)") (class "Default")
      (node (ref "R95") (pin "1") (pinfunction "1_1") (pintype "passive"))
      (node (ref "U8") (pin "9") (pinfunction "~{Y}6_9") (pintype "output"))
    )
    (net (code "109") (name "Net-(U8-~{Y}7)") (class "Default")
      (node (ref "R96") (pin "1") (pinfunction "1_1") (pintype "passive"))
      (node (ref "U8") (pin "7") (pinfunction "~{Y}7_7") (pintype "output"))
    )
    (net (code "110") (name "VCC") (class "Default")
      (node (ref "C1") (pin "1") (pinfunction "1_1") (pintype "passive"))
      (node (ref "C14") (pin "1") (pinfunction "1_1") (pintype "passive"))
      (node (ref "C15") (pin "1") (pinfunction "1_1") (pintype "passive"))
      (node (ref "C2") (pin "1") (pinfunction "1_1") (pintype "passive"))
      (node (ref "C3") (pin "2") (pinfunction "2_2") (pintype "passive"))
      (node (ref "C4") (pin "2") (pinfunction "2_2") (pintype "passive"))
      (node (ref "C5") (pin "2") (pinfunction "2_2") (pintype "passive"))
      (node (ref "J1") (pin "8") (pinfunction "8_8") (pintype "passive"))
      (node (ref "Q1") (pin "2") (pinfunction "E_2") (pintype "passive"))
      (node (ref "Q10") (pin "2") (pinfunction "E_2") (pintype "passive"))
      (node (ref "Q11") (pin "2") (pinfunction "E_2") (pintype "passive"))
      (node (ref "Q2") (pin "2") (pinfunction "E_2") (pintype "passive"))
      (node (ref "Q22") (pin "2") (pinfunction "E_2") (pintype "passive"))
      (node (ref "Q23") (pin "2") (pinfunction "E_2") (pintype "passive"))
      (node (ref "Q24") (pin "2") (pinfunction "E_2") (pintype "passive"))
      (node (ref "Q25") (pin "2") (pinfunction "E_2") (pintype "passive"))
      (node (ref "Q26") (pin "2") (pinfunction "E_2") (pintype "passive"))
      (node (ref "Q3") (pin "2") (pinfunction "E_2") (pintype "passive"))
      (node (ref "Q4") (pin "2") (pinfunction "E_2") (pintype "passive"))
      (node (ref "Q5") (pin "2") (pinfunction "E_2") (pintype "passive"))
      (node (ref "Q6") (pin "2") (pinfunction "E_2") (pintype "passive"))
      (node (ref "Q7") (pin "2") (pinfunction "E_2") (pintype "passive"))
      (node (ref "Q8") (pin "2") (pinfunction "E_2") (pintype "passive"))
      (node (ref "Q9") (pin "2") (pinfunction "E_2") (pintype "passive"))
      (node (ref "R36") (pin "1") (pinfunction "1_1") (pintype "passive"))
      (node (ref "R37") (pin "1") (pinfunction "1_1") (pintype "passive"))
      (node (ref "R38") (pin "1") (pinfunction "1_1") (pintype "passive"))
      (node (ref "R39") (pin "1") (pinfunction "1_1") (pintype "passive"))
      (node (ref "R40") (pin "1") (pinfunction "1_1") (pintype "passive"))
      (node (ref "R41") (pin "1") (pinfunction "1_1") (pintype "passive"))
      (node (ref "R42") (pin "1") (pinfunction "1_1") (pintype "passive"))
      (node (ref "R43") (pin "1") (pinfunction "1_1") (pintype "passive"))
      (node (ref "R44") (pin "1") (pinfunction "1_1") (pintype "passive"))
      (node (ref "R45") (pin "1") (pinfunction "1_1") (pintype "passive"))
      (node (ref "R46") (pin "1") (pinfunction "1_1") (pintype "passive"))
      (node (ref "R82") (pin "1") (pinfunction "1_1") (pintype "passive"))
      (node (ref "R83") (pin "1") (pinfunction "1_1") (pintype "passive"))
      (node (ref "R84") (pin "1") (pinfunction "1_1") (pintype "passive"))
      (node (ref "R85") (pin "1") (pinfunction "1_1") (pintype "passive"))
      (node (ref "R86") (pin "1") (pinfunction "1_1") (pintype "passive"))
      (node (ref "U1") (pin "16") (pinfunction "VCC_16") (pintype "power_in"))
      (node (ref "U1") (pin "6") (pinfunction "OE1_6") (pintype "input"))
      (node (ref "U2") (pin "10") (pinfunction "~{SRCLR}_10") (pintype "input"))
      (node (ref "U2") (pin "16") (pinfunction "VCC_16") (pintype "power_in"))
      (node (ref "U3") (pin "10") (pinfunction "~{SRCLR}_10") (pintype "input"))
      (node (ref "U3") (pin "16") (pinfunction "VCC_16") (pintype "power_in"))
      (node (ref "U4") (pin "10") (pinfunction "~{SRCLR}_10") (pintype "input"))
      (node (ref "U4") (pin "16") (pinfunction "VCC_16") (pintype "power_in"))
      (node (ref "U8") (pin "16") (pinfunction "VCC_16") (pintype "power_in"))
    )
    (net (code "111") (name "unconnected-(U4-QH'-Pad9)") (class "Default")
      (node (ref "U4") (pin "9") (pinfunction "QH'_9") (pintype "output"))
    )
  )
)
